# nxp_simplified.net
KiCad netlist of a schematic drawn in EAGLE
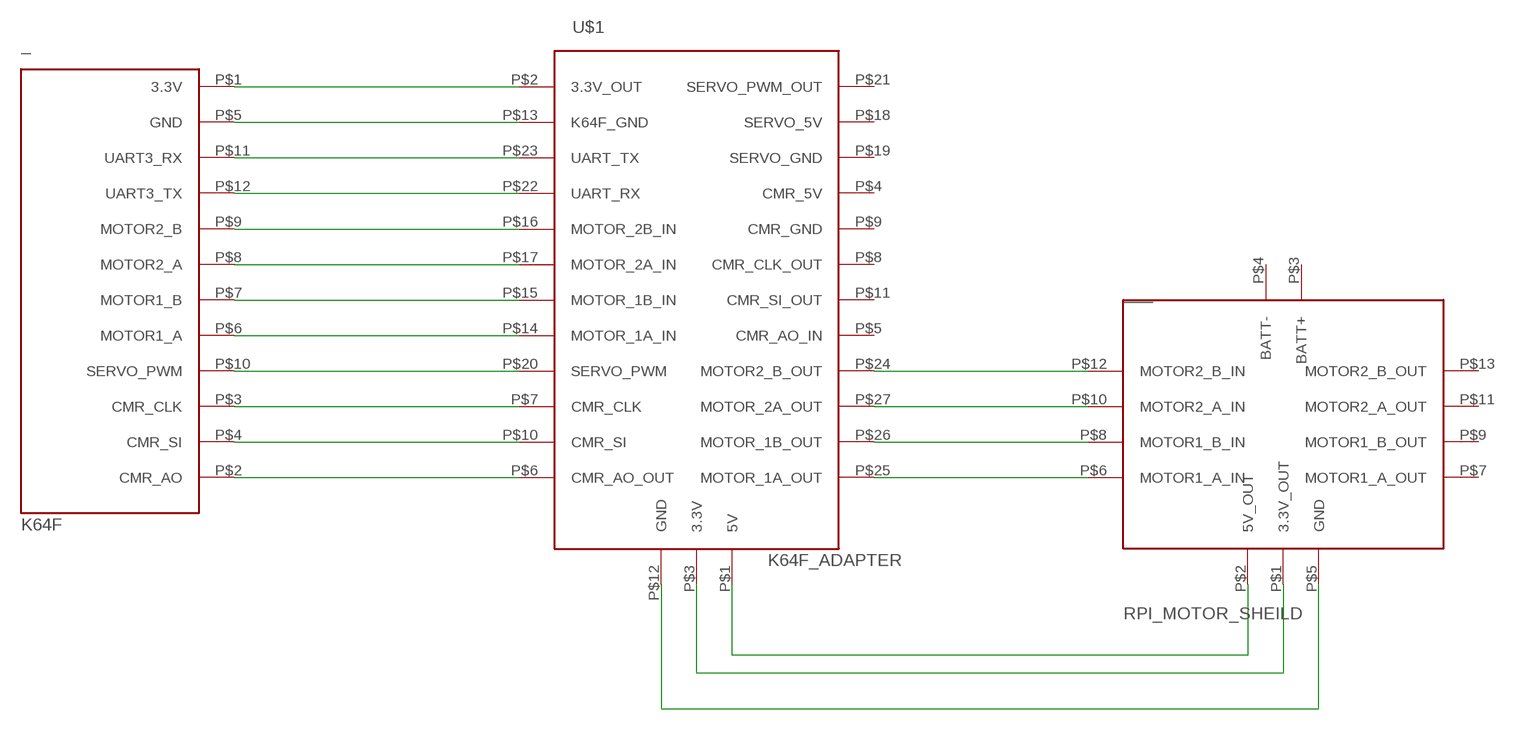
[diagram p0: schematic, sheet 1]

(export (version "E")
  (design (tool "Eeschema 10.0.6"))
  (components
    (comp (ref "U$1")
      (value "K64F_ADAPTER")
      (footprint "eagle-import:K64F_ADAPTER")
      (libsource (lib "eagle-import") (part "K64F_ADAPTER"))
    )
    (comp (ref "_")
      (value "K64F")
      (footprint "eagle-import:K64F")
      (libsource (lib "eagle-import") (part "K64F"))
    )
    (comp (ref "___")
      (value "RPI_MOTOR_SHEILD")
      (footprint "eagle-import:RPI_MOTOR_SHEILD")
      (libsource (lib "eagle-import") (part "RPI_MOTOR_SHEILD"))
    )
  )
  (nets
    (net (code "1") (name "Net-(U$1-3.3V)") (class "Default")
      (node (ref "U$1") (pin "P$3") (pinfunction "3.3V_P$3") (pintype "bidirectional"))
      (node (ref "___") (pin "P$1") (pinfunction "3.3V_OUT_P$1") (pintype "bidirectional"))
    )
    (net (code "2") (name "Net-(U$1-3.3V_OUT)") (class "Default")
      (node (ref "U$1") (pin "P$2") (pinfunction "3.3V_OUT_P$2") (pintype "bidirectional"))
      (node (ref "_") (pin "P$1") (pinfunction "3.3V_P$1") (pintype "bidirectional"))
    )
    (net (code "3") (name "Net-(U$1-5V)") (class "Default")
      (node (ref "U$1") (pin "P$1") (pinfunction "5V_P$1") (pintype "bidirectional"))
      (node (ref "___") (pin "P$2") (pinfunction "5V_OUT_P$2") (pintype "bidirectional"))
    )
    (net (code "4") (name "Net-(U$1-CMR_AO_OUT)") (class "Default")
      (node (ref "U$1") (pin "P$6") (pinfunction "CMR_AO_OUT_P$6") (pintype "bidirectional"))
      (node (ref "_") (pin "P$2") (pinfunction "CMR_AO_P$2") (pintype "bidirectional"))
    )
    (net (code "5") (name "Net-(U$1-CMR_CLK)") (class "Default")
      (node (ref "U$1") (pin "P$7") (pinfunction "CMR_CLK_P$7") (pintype "bidirectional"))
      (node (ref "_") (pin "P$3") (pinfunction "CMR_CLK_P$3") (pintype "bidirectional"))
    )
    (net (code "6") (name "Net-(U$1-CMR_SI)") (class "Default")
      (node (ref "U$1") (pin "P$10") (pinfunction "CMR_SI_P$10") (pintype "bidirectional"))
      (node (ref "_") (pin "P$4") (pinfunction "CMR_SI_P$4") (pintype "bidirectional"))
    )
    (net (code "7") (name "Net-(U$1-GND)") (class "Default")
      (node (ref "U$1") (pin "P$12") (pinfunction "GND_P$12") (pintype "bidirectional"))
      (node (ref "___") (pin "P$5") (pinfunction "GND_P$5") (pintype "bidirectional"))
    )
    (net (code "8") (name "Net-(U$1-K64F_GND)") (class "Default")
      (node (ref "U$1") (pin "P$13") (pinfunction "K64F_GND_P$13") (pintype "bidirectional"))
      (node (ref "_") (pin "P$5") (pinfunction "GND_P$5") (pintype "bidirectional"))
    )
    (net (code "9") (name "Net-(U$1-MOTOR2_B_OUT)") (class "Default")
      (node (ref "U$1") (pin "P$24") (pinfunction "MOTOR2_B_OUT_P$24") (pintype "bidirectional"))
      (node (ref "___") (pin "P$12") (pinfunction "MOTOR2_B_IN_P$12") (pintype "bidirectional"))
    )
    (net (code "10") (name "Net-(U$1-MOTOR_1A_IN)") (class "Default")
      (node (ref "U$1") (pin "P$14") (pinfunction "MOTOR_1A_IN_P$14") (pintype "bidirectional"))
      (node (ref "_") (pin "P$6") (pinfunction "MOTOR1_A_P$6") (pintype "bidirectional"))
    )
    (net (code "11") (name "Net-(U$1-MOTOR_1A_OUT)") (class "Default")
      (node (ref "U$1") (pin "P$25") (pinfunction "MOTOR_1A_OUT_P$25") (pintype "bidirectional"))
      (node (ref "___") (pin "P$6") (pinfunction "MOTOR1_A_IN_P$6") (pintype "bidirectional"))
    )
    (net (code "12") (name "Net-(U$1-MOTOR_1B_IN)") (class "Default")
      (node (ref "U$1") (pin "P$15") (pinfunction "MOTOR_1B_IN_P$15") (pintype "bidirectional"))
      (node (ref "_") (pin "P$7") (pinfunction "MOTOR1_B_P$7") (pintype "bidirectional"))
    )
    (net (code "13") (name "Net-(U$1-MOTOR_1B_OUT)") (class "Default")
      (node (ref "U$1") (pin "P$26") (pinfunction "MOTOR_1B_OUT_P$26") (pintype "bidirectional"))
      (node (ref "___") (pin "P$8") (pinfunction "MOTOR1_B_IN_P$8") (pintype "bidirectional"))
    )
    (net (code "14") (name "Net-(U$1-MOTOR_2A_IN)") (class "Default")
      (node (ref "U$1") (pin "P$17") (pinfunction "MOTOR_2A_IN_P$17") (pintype "bidirectional"))
      (node (ref "_") (pin "P$8") (pinfunction "MOTOR2_A_P$8") (pintype "bidirectional"))
    )
    (net (code "15") (name "Net-(U$1-MOTOR_2A_OUT)") (class "Default")
      (node (ref "U$1") (pin "P$27") (pinfunction "MOTOR_2A_OUT_P$27") (pintype "bidirectional"))
      (node (ref "___") (pin "P$10") (pinfunction "MOTOR2_A_IN_P$10") (pintype "bidirectional"))
    )
    (net (code "16") (name "Net-(U$1-MOTOR_2B_IN)") (class "Default")
      (node (ref "U$1") (pin "P$16") (pinfunction "MOTOR_2B_IN_P$16") (pintype "bidirectional"))
      (node (ref "_") (pin "P$9") (pinfunction "MOTOR2_B_P$9") (pintype "bidirectional"))
    )
    (net (code "17") (name "Net-(U$1-SERVO_PWM)") (class "Default")
      (node (ref "U$1") (pin "P$20") (pinfunction "SERVO_PWM_P$20") (pintype "bidirectional"))
      (node (ref "_") (pin "P$10") (pinfunction "SERVO_PWM_P$10") (pintype "bidirectional"))
    )
    (net (code "18") (name "Net-(U$1-UART_RX)") (class "Default")
      (node (ref "U$1") (pin "P$22") (pinfunction "UART_RX_P$22") (pintype "bidirectional"))
      (node (ref "_") (pin "P$12") (pinfunction "UART3_TX_P$12") (pintype "bidirectional"))
    )
    (net (code "19") (name "Net-(U$1-UART_TX)") (class "Default")
      (node (ref "U$1") (pin "P$23") (pinfunction "UART_TX_P$23") (pintype "bidirectional"))
      (node (ref "_") (pin "P$11") (pinfunction "UART3_RX_P$11") (pintype "bidirectional"))
    )
    (net (code "20") (name "unconnected-(U$1-CMR_5V-PadP$4)") (class "Default")
      (node (ref "U$1") (pin "P$4") (pinfunction "CMR_5V_P$4") (pintype "bidirectional"))
    )
    (net (code "21") (name "unconnected-(U$1-CMR_AO_IN-PadP$5)") (class "Default")
      (node (ref "U$1") (pin "P$5") (pinfunction "CMR_AO_IN_P$5") (pintype "bidirectional"))
    )
    (net (code "22") (name "unconnected-(U$1-CMR_CLK_OUT-PadP$8)") (class "Default")
      (node (ref "U$1") (pin "P$8") (pinfunction "CMR_CLK_OUT_P$8") (pintype "bidirectional"))
    )
    (net (code "23") (name "unconnected-(U$1-CMR_GND-PadP$9)") (class "Default")
      (node (ref "U$1") (pin "P$9") (pinfunction "CMR_GND_P$9") (pintype "bidirectional"))
    )
    (net (code "24") (name "unconnected-(U$1-CMR_SI_OUT-PadP$11)") (class "Default")
      (node (ref "U$1") (pin "P$11") (pinfunction "CMR_SI_OUT_P$11") (pintype "bidirectional"))
    )
    (net (code "25") (name "unconnected-(U$1-SERVO_5V-PadP$18)") (class "Default")
      (node (ref "U$1") (pin "P$18") (pinfunction "SERVO_5V_P$18") (pintype "bidirectional"))
    )
    (net (code "26") (name "unconnected-(U$1-SERVO_GND-PadP$19)") (class "Default")
      (node (ref "U$1") (pin "P$19") (pinfunction "SERVO_GND_P$19") (pintype "bidirectional"))
    )
    (net (code "27") (name "unconnected-(U$1-SERVO_PWM_OUT-PadP$21)") (class "Default")
      (node (ref "U$1") (pin "P$21") (pinfunction "SERVO_PWM_OUT_P$21") (pintype "bidirectional"))
    )
    (net (code "28") (name "unconnected-(___-BATT+-PadP$3)") (class "Default")
      (node (ref "___") (pin "P$3") (pinfunction "BATT+_P$3") (pintype "bidirectional"))
    )
    (net (code "29") (name "unconnected-(___-BATT--PadP$4)") (class "Default")
      (node (ref "___") (pin "P$4") (pinfunction "BATT-_P$4") (pintype "bidirectional"))
    )
    (net (code "30") (name "unconnected-(___-MOTOR1_A_OUT-PadP$7)") (class "Default")
      (node (ref "___") (pin "P$7") (pinfunction "MOTOR1_A_OUT_P$7") (pintype "bidirectional"))
    )
    (net (code "31") (name "unconnected-(___-MOTOR1_B_OUT-PadP$9)") (class "Default")
      (node (ref "___") (pin "P$9") (pinfunction "MOTOR1_B_OUT_P$9") (pintype "bidirectional"))
    )
    (net (code "32") (name "unconnected-(___-MOTOR2_A_OUT-PadP$11)") (class "Default")
      (node (ref "___") (pin "P$11") (pinfunction "MOTOR2_A_OUT_P$11") (pintype "bidirectional"))
    )
    (net (code "33") (name "unconnected-(___-MOTOR2_B_OUT-PadP$13)") (class "Default")
      (node (ref "___") (pin "P$13") (pinfunction "MOTOR2_B_OUT_P$13") (pintype "bidirectional"))
    )
  )
)
